# GBE1_PHY.net
KiCad netlist of a schematic drawn in Altium Designer
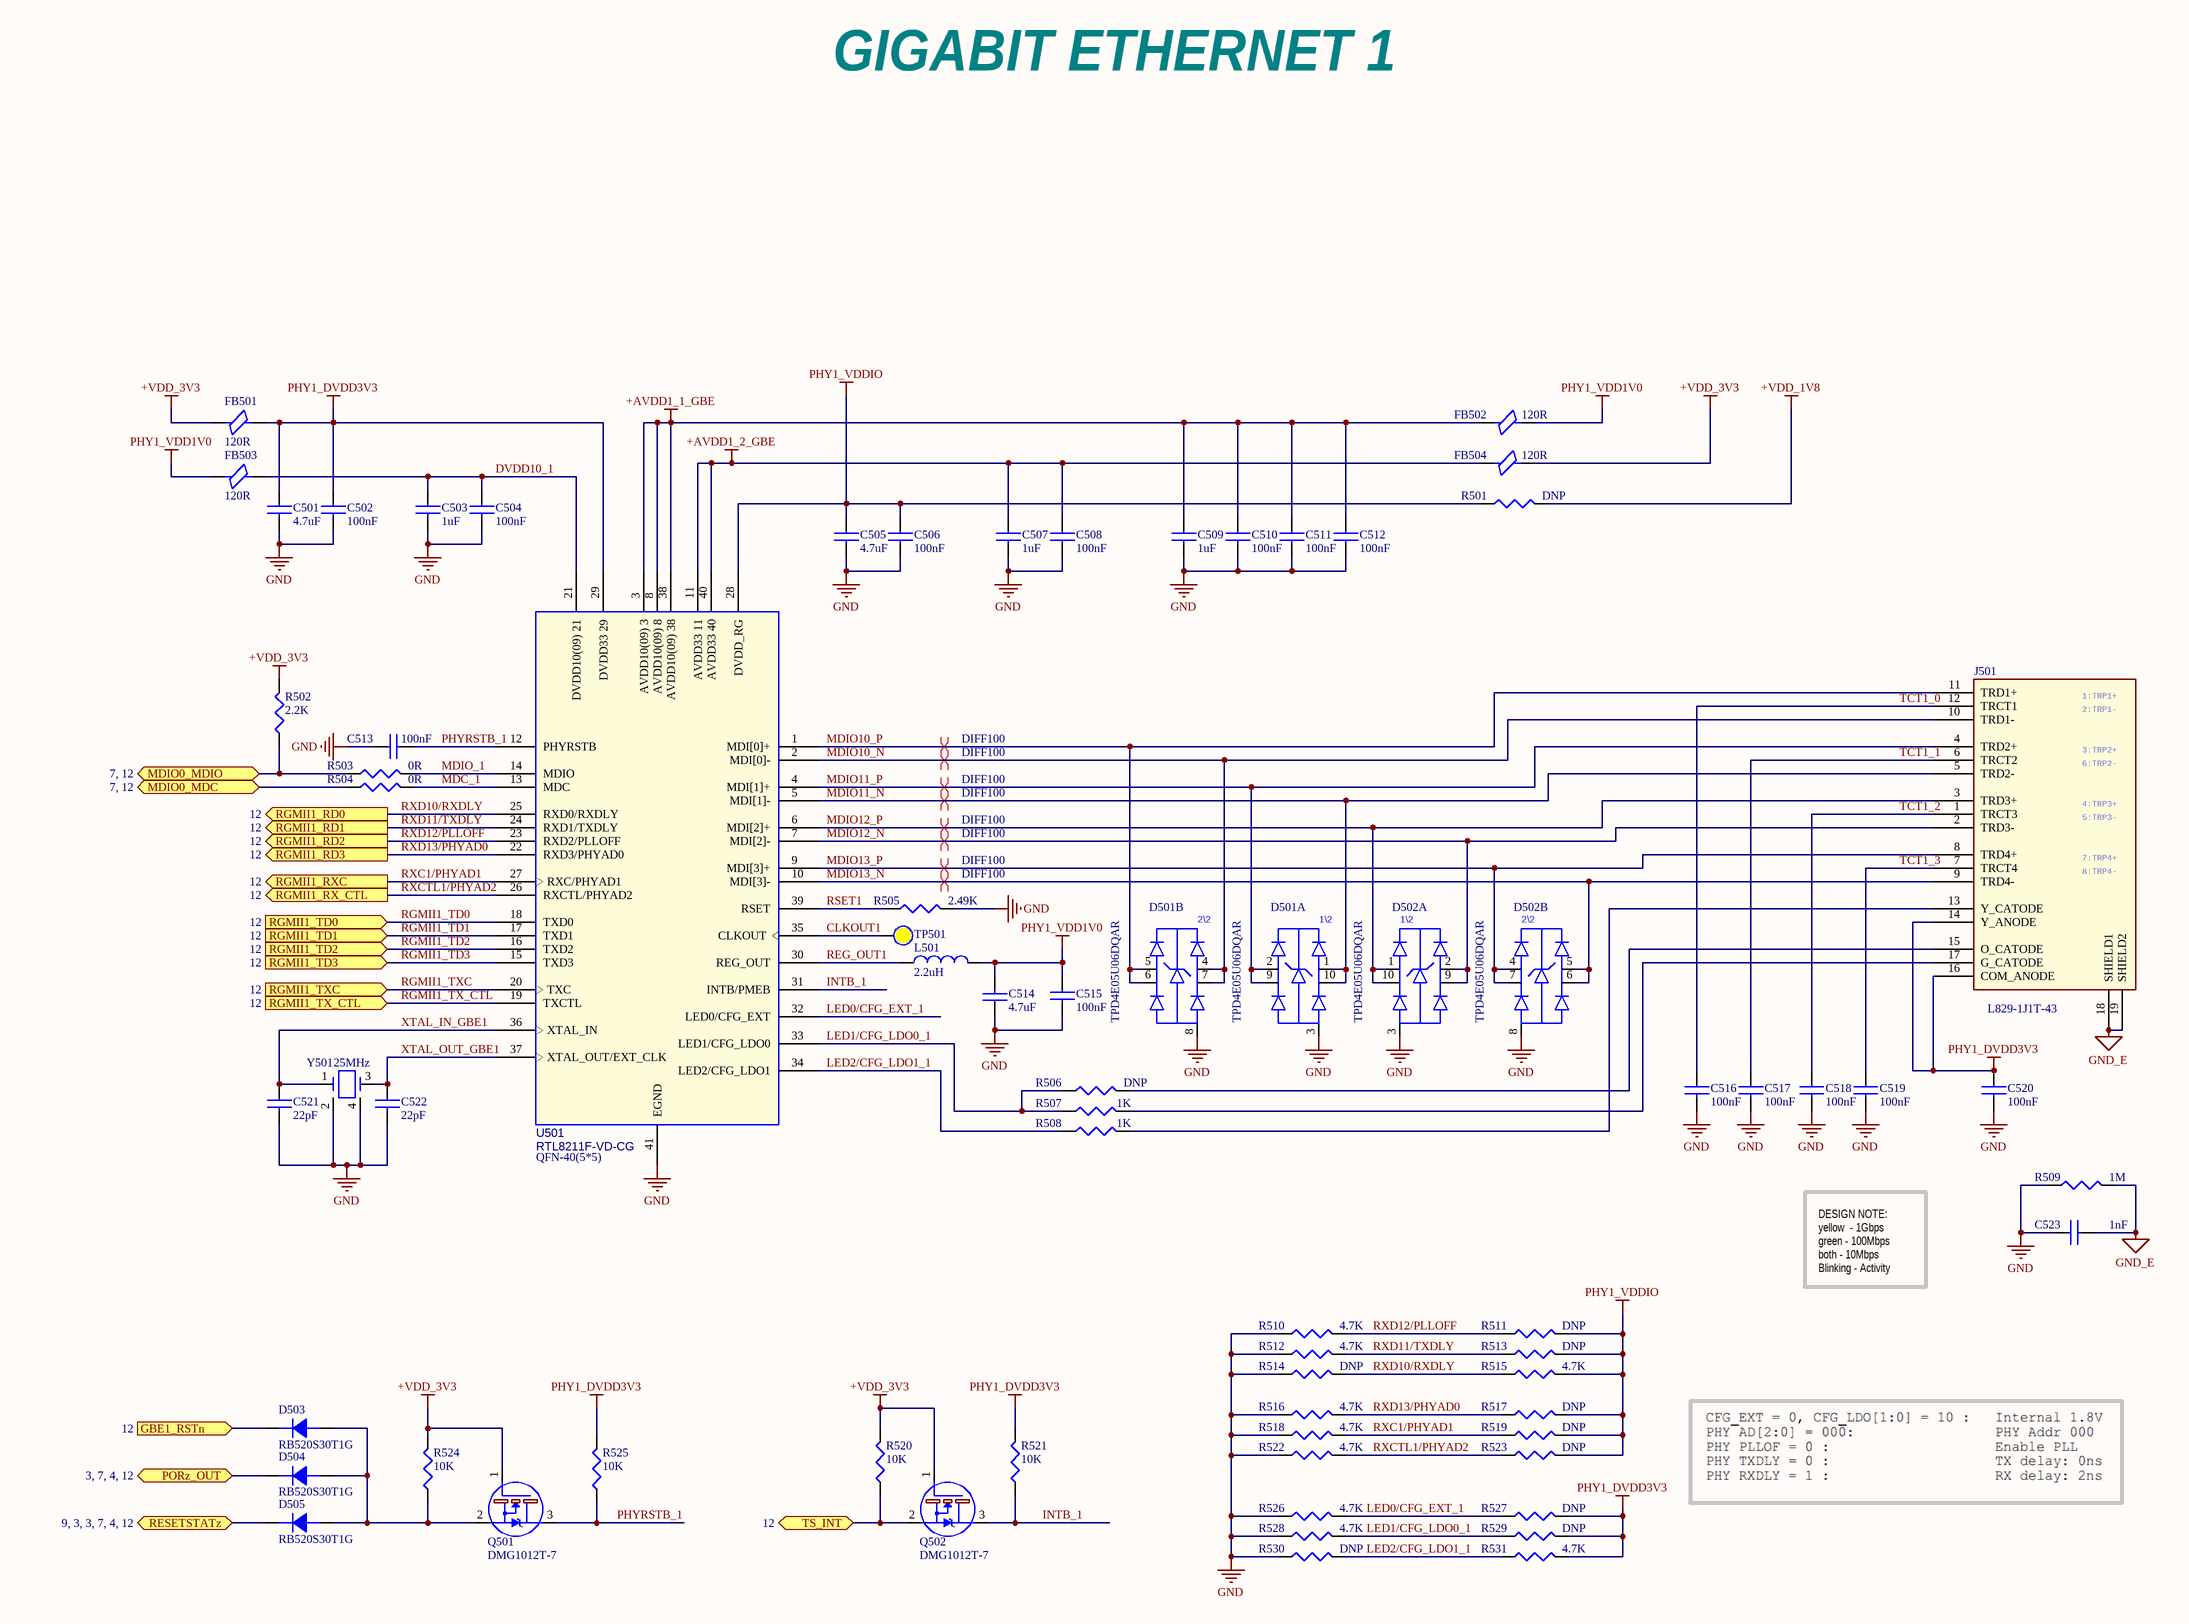
[diagram p0: GBE1 PHY.SchDoc]

(export (version "E")
  (design (tool "Eeschema 10.0.6"))
  (components
    (comp (ref "C501")
      (value "4.7uF")
      (footprint "C0402")
      (description "Multilayer Ceramic Capacitor, 4.7 uF, 6.3V, ± 10%, X5R, 0402 [1005 Metric]")
      (fields
        (field (name "MANUFACTURER") "Yageo")
        (field (name "MANUFACTURER PART NUMBER") "CC0402MRX5R5BB475")
      )
      (libsource (lib "Schlib SOM AM625") (part "CC0402MRX5R5BB475"))
    )
    (comp (ref "C502")
      (value "100nF")
      (footprint "C0201")
      (description "Multilayer Ceramic Capacitor, 0.1 uF, 16 V, ± 10%, X5R, 0201 [0603 Metric]")
      (fields
        (field (name "MANUFACTURER") "Yageo")
        (field (name "MANUFACTURER PART NUMBER") "CC0201KRX5R6BB104")
      )
      (libsource (lib "Schlib SOM AM625") (part "CC0201KRX5R6BB104"))
    )
    (comp (ref "C503")
      (value "1uF")
      (footprint "C0201")
      (description "1 µF ±20% 6.3V Ceramic Capacitor X5R 0201 (0603 Metric)")
      (fields
        (field (name "MANUFACTURER") "Yageo")
        (field (name "MANUFACTURER PART NUMBER") "CC0201MRX5R5BB105")
      )
      (libsource (lib "Schlib SOM AM625") (part "CC0201MRX5R5BB105"))
    )
    (comp (ref "C504")
      (value "100nF")
      (footprint "C0201")
      (description "Multilayer Ceramic Capacitor, 0.1 uF, 16 V, ± 10%, X5R, 0201 [0603 Metric]")
      (fields
        (field (name "MANUFACTURER") "Yageo")
        (field (name "MANUFACTURER PART NUMBER") "CC0201KRX5R6BB104")
      )
      (libsource (lib "Schlib SOM AM625") (part "CC0201KRX5R6BB104"))
    )
    (comp (ref "C505")
      (value "4.7uF")
      (footprint "C0402")
      (description "Multilayer Ceramic Capacitor, 4.7 uF, 6.3V, ± 10%, X5R, 0402 [1005 Metric]")
      (fields
        (field (name "MANUFACTURER") "Yageo")
        (field (name "MANUFACTURER PART NUMBER") "CC0402MRX5R5BB475")
      )
      (libsource (lib "Schlib SOM AM625") (part "CC0402MRX5R5BB475"))
    )
    (comp (ref "C506")
      (value "100nF")
      (footprint "C0201")
      (description "Multilayer Ceramic Capacitor, 0.1 uF, 16 V, ± 10%, X5R, 0201 [0603 Metric]")
      (fields
        (field (name "MANUFACTURER") "Yageo")
        (field (name "MANUFACTURER PART NUMBER") "CC0201KRX5R6BB104")
      )
      (libsource (lib "Schlib SOM AM625") (part "CC0201KRX5R6BB104"))
    )
    (comp (ref "C507")
      (value "1uF")
      (footprint "C0201")
      (description "1 µF ±20% 6.3V Ceramic Capacitor X5R 0201 (0603 Metric)")
      (fields
        (field (name "MANUFACTURER") "Yageo")
        (field (name "MANUFACTURER PART NUMBER") "CC0201MRX5R5BB105")
      )
      (libsource (lib "Schlib SOM AM625") (part "CC0201MRX5R5BB105"))
    )
    (comp (ref "C508")
      (value "100nF")
      (footprint "C0201")
      (description "Multilayer Ceramic Capacitor, 0.1 uF, 16 V, ± 10%, X5R, 0201 [0603 Metric]")
      (fields
        (field (name "MANUFACTURER") "Yageo")
        (field (name "MANUFACTURER PART NUMBER") "CC0201KRX5R6BB104")
      )
      (libsource (lib "Schlib SOM AM625") (part "CC0201KRX5R6BB104"))
    )
    (comp (ref "C509")
      (value "1uF")
      (footprint "C0201")
      (description "1 µF ±20% 6.3V Ceramic Capacitor X5R 0201 (0603 Metric)")
      (fields
        (field (name "MANUFACTURER") "Yageo")
        (field (name "MANUFACTURER PART NUMBER") "CC0201MRX5R5BB105")
      )
      (libsource (lib "Schlib SOM AM625") (part "CC0201MRX5R5BB105"))
    )
    (comp (ref "C510")
      (value "100nF")
      (footprint "C0201")
      (description "Multilayer Ceramic Capacitor, 0.1 uF, 16 V, ± 10%, X5R, 0201 [0603 Metric]")
      (fields
        (field (name "MANUFACTURER") "Yageo")
        (field (name "MANUFACTURER PART NUMBER") "CC0201KRX5R6BB104")
      )
      (libsource (lib "Schlib SOM AM625") (part "CC0201KRX5R6BB104"))
    )
    (comp (ref "C511")
      (value "100nF")
      (footprint "C0201")
      (description "Multilayer Ceramic Capacitor, 0.1 uF, 16 V, ± 10%, X5R, 0201 [0603 Metric]")
      (fields
        (field (name "MANUFACTURER") "Yageo")
        (field (name "MANUFACTURER PART NUMBER") "CC0201KRX5R6BB104")
      )
      (libsource (lib "Schlib SOM AM625") (part "CC0201KRX5R6BB104"))
    )
    (comp (ref "C512")
      (value "100nF")
      (footprint "C0201")
      (description "Multilayer Ceramic Capacitor, 0.1 uF, 16 V, ± 10%, X5R, 0201 [0603 Metric]")
      (fields
        (field (name "MANUFACTURER") "Yageo")
        (field (name "MANUFACTURER PART NUMBER") "CC0201KRX5R6BB104")
      )
      (libsource (lib "Schlib SOM AM625") (part "CC0201KRX5R6BB104"))
    )
    (comp (ref "C513")
      (value "100nF")
      (footprint "C0201")
      (description "Multilayer Ceramic Capacitor, 0.1 uF, 16 V, ± 10%, X5R, 0201 [0603 Metric]")
      (fields
        (field (name "MANUFACTURER") "Yageo")
        (field (name "MANUFACTURER PART NUMBER") "CC0201KRX5R6BB104")
      )
      (libsource (lib "Schlib SOM AM625") (part "CC0201KRX5R6BB104"))
    )
    (comp (ref "C514")
      (value "4.7uF")
      (footprint "C0402")
      (description "Multilayer Ceramic Capacitor, 4.7 uF, 6.3V, ± 10%, X5R, 0402 [1005 Metric]")
      (fields
        (field (name "MANUFACTURER") "Yageo")
        (field (name "MANUFACTURER PART NUMBER") "CC0402MRX5R5BB475")
      )
      (libsource (lib "Schlib SOM AM625") (part "CC0402MRX5R5BB475"))
    )
    (comp (ref "C515")
      (value "100nF")
      (footprint "C0201")
      (description "Multilayer Ceramic Capacitor, 0.1 uF, 16 V, ± 10%, X5R, 0201 [0603 Metric]")
      (fields
        (field (name "MANUFACTURER") "Yageo")
        (field (name "MANUFACTURER PART NUMBER") "CC0201KRX5R6BB104")
      )
      (libsource (lib "Schlib SOM AM625") (part "CC0201KRX5R6BB104"))
    )
    (comp (ref "C516")
      (value "100nF")
      (footprint "C0402")
      (description "Multilayer Ceramic Capacitor, 0.1 uF, 50 V, ± 10%, X5R, 0402 [1005 Metric]")
      (fields
        (field (name "MANUFACTURER") "TDK")
        (field (name "MANUFACTURER PART NUMBER") "C1005X5R1H104K050BB")
      )
      (libsource (lib "Schlib SOM AM625") (part "C1005X5R1H104K050BB"))
    )
    (comp (ref "C517")
      (value "100nF")
      (footprint "C0402")
      (description "Multilayer Ceramic Capacitor, 0.1 uF, 50 V, ± 10%, X5R, 0402 [1005 Metric]")
      (fields
        (field (name "MANUFACTURER") "TDK")
        (field (name "MANUFACTURER PART NUMBER") "C1005X5R1H104K050BB")
      )
      (libsource (lib "Schlib SOM AM625") (part "C1005X5R1H104K050BB"))
    )
    (comp (ref "C518")
      (value "100nF")
      (footprint "C0402")
      (description "Multilayer Ceramic Capacitor, 0.1 uF, 50 V, ± 10%, X5R, 0402 [1005 Metric]")
      (fields
        (field (name "MANUFACTURER") "TDK")
        (field (name "MANUFACTURER PART NUMBER") "C1005X5R1H104K050BB")
      )
      (libsource (lib "Schlib SOM AM625") (part "C1005X5R1H104K050BB"))
    )
    (comp (ref "C519")
      (value "100nF")
      (footprint "C0402")
      (description "Multilayer Ceramic Capacitor, 0.1 uF, 50 V, ± 10%, X5R, 0402 [1005 Metric]")
      (fields
        (field (name "MANUFACTURER") "TDK")
        (field (name "MANUFACTURER PART NUMBER") "C1005X5R1H104K050BB")
      )
      (libsource (lib "Schlib SOM AM625") (part "C1005X5R1H104K050BB"))
    )
    (comp (ref "C520")
      (value "100nF")
      (footprint "C0402")
      (description "Multilayer Ceramic Capacitor, 0.1 uF, 50 V, ± 10%, X5R, 0402 [1005 Metric]")
      (fields
        (field (name "MANUFACTURER") "TDK")
        (field (name "MANUFACTURER PART NUMBER") "C1005X5R1H104K050BB")
      )
      (libsource (lib "Schlib SOM AM625") (part "C1005X5R1H104K050BB"))
    )
    (comp (ref "C521")
      (value "22pF")
      (footprint "C0201")
      (description "0201 22 pF 50 V ±5 % Tolerance NP0 SMT Multilayer Ceramic Capacitor")
      (fields
        (field (name "MANUFACTURER") "Yageo")
        (field (name "MANUFACTURER PART NUMBER") "CC0201JRNPO9BN220")
      )
      (libsource (lib "Schlib SOM AM625") (part "CC0201JRNPO9BN220"))
    )
    (comp (ref "C522")
      (value "22pF")
      (footprint "C0201")
      (description "0201 22 pF 50 V ±5 % Tolerance NP0 SMT Multilayer Ceramic Capacitor")
      (fields
        (field (name "MANUFACTURER") "Yageo")
        (field (name "MANUFACTURER PART NUMBER") "CC0201JRNPO9BN220")
      )
      (libsource (lib "Schlib SOM AM625") (part "CC0201JRNPO9BN220"))
    )
    (comp (ref "C523")
      (value "1nF")
      (footprint "C1206B/3216MM")
      (description "Cap Ceramic 0.001uF 1000V X7R 10% Pad SMD 1206 125°C Low ESR Automotive Medical T/R")
      (fields
        (field (name "MANUFACTURER") "KEMET")
        (field (name "MANUFACTURER PART NUMBER") "C1206C102KDRACAUTO")
      )
      (libsource (lib "Schlib SOM AM625") (part "C1206C102KDRACAUTO"))
    )
    (comp (ref "D501")
      (value "TPD4E05U06DQAR")
      (footprint "10-USON")
      (description "Quad 0.5-pF, 5.5-V, ±12-kV ESD protection diode for USB, HDMI & High Speed Interfaces")
      (fields (field (name "MANUFACTURER") "Texas Instruments"))
      (libsource (lib "Schlib SOM AM625") (part "TPD4E05U06DQAR"))
    )
    (comp (ref "D502")
      (value "TPD4E05U06DQAR")
      (footprint "10-USON")
      (description "Quad 0.5-pF, 5.5-V, ±12-kV ESD protection diode for USB, HDMI & High Speed Interfaces")
      (fields (field (name "MANUFACTURER") "Texas Instruments"))
      (libsource (lib "Schlib SOM AM625") (part "TPD4E05U06DQAR"))
    )
    (comp (ref "D503")
      (value "RB520S30T1G")
      (footprint "sod_523")
      (description "Diode Schottky 30V 0.2A 2-Pin SOD-523 T/R - Product that comes on tape, but is not reeled")
      (fields (field (name "MANUFACTURER") "ON Semiconductor"))
      (libsource (lib "Schlib SOM AM625") (part "RB520S30T1G"))
    )
    (comp (ref "D504")
      (value "RB520S30T1G")
      (footprint "sod_523")
      (description "Diode Schottky 30V 0.2A 2-Pin SOD-523 T/R - Product that comes on tape, but is not reeled")
      (fields (field (name "MANUFACTURER") "ON Semiconductor"))
      (libsource (lib "Schlib SOM AM625") (part "RB520S30T1G"))
    )
    (comp (ref "D505")
      (value "RB520S30T1G")
      (footprint "sod_523")
      (description "Diode Schottky 30V 0.2A 2-Pin SOD-523 T/R - Product that comes on tape, but is not reeled")
      (fields (field (name "MANUFACTURER") "ON Semiconductor"))
      (libsource (lib "Schlib SOM AM625") (part "RB520S30T1G"))
    )
    (comp (ref "FB501")
      (value "120R")
      (footprint "FB0402")
      (description "Ferrite Beads Multi-Layer 120Ohm 25% 100MHz 1.3A 0.09Ohm DCR 0402 Automotive T/R")
      (fields
        (field (name "MANUFACTURER") "Murata")
        (field (name "MANUFACTURER PART NUMBER") "BLM15PD121SZ1D")
      )
      (libsource (lib "Schlib SOM AM625") (part "BLM15PD121SZ1D"))
    )
    (comp (ref "FB502")
      (value "120R")
      (footprint "FB0402")
      (description "Ferrite Beads Multi-Layer 120Ohm 25% 100MHz 1.3A 0.09Ohm DCR 0402 Automotive T/R")
      (fields
        (field (name "MANUFACTURER") "Murata")
        (field (name "MANUFACTURER PART NUMBER") "BLM15PD121SZ1D")
      )
      (libsource (lib "Schlib SOM AM625") (part "BLM15PD121SZ1D"))
    )
    (comp (ref "FB503")
      (value "120R")
      (footprint "FB0402")
      (description "Ferrite Beads Multi-Layer 120Ohm 25% 100MHz 1.3A 0.09Ohm DCR 0402 Automotive T/R")
      (fields
        (field (name "MANUFACTURER") "Murata")
        (field (name "MANUFACTURER PART NUMBER") "BLM15PD121SZ1D")
      )
      (libsource (lib "Schlib SOM AM625") (part "BLM15PD121SZ1D"))
    )
    (comp (ref "FB504")
      (value "120R")
      (footprint "FB0402")
      (description "Ferrite Beads Multi-Layer 120Ohm 25% 100MHz 1.3A 0.09Ohm DCR 0402 Automotive T/R")
      (fields
        (field (name "MANUFACTURER") "Murata")
        (field (name "MANUFACTURER PART NUMBER") "BLM15PD121SZ1D")
      )
      (libsource (lib "Schlib SOM AM625") (part "BLM15PD121SZ1D"))
    )
    (comp (ref "J501")
      (value "L829-1J1T-43")
      (footprint "L829-1J1T-43")
      (description "CONN MAGJACK 1PORT SHLD 1000BT")
      (fields
        (field (name "MANUFACTURER") "Bel Fuse Inc")
        (field (name ".CHECKED PCB") "RF")
        (field (name ".CHECKED SCH") "RF")
      )
      (libsource (lib "Schlib SOM AM625") (part "L829-1J1T-43"))
    )
    (comp (ref "L501")
      (value "2.2uH")
      (footprint "l2016")
      (description "Inductor Power Shielded Wirewound 2.2uH 20% 1MHz Metal 1.4A 0.168Ohm DCR 0806 T/R")
      (fields
        (field (name "MANUFACTURER") "Murata")
        (field (name "MANUFACTURER PART NUMBER") "DFE201610P-2R2M=P2")
      )
      (libsource (lib "Schlib SOM AM625") (part "DFE201610P-2R2M=P2"))
    )
    (comp (ref "Q501")
      (value "DMG1012T-7")
      (footprint "sot_523")
      (description "Transistor MOSFET NTR4003NT1G, SOT23, ON Semi")
      (fields (field (name "MANUFACTURER") "Diodes"))
      (libsource (lib "Schlib SOM AM625") (part "DMG1012T-7"))
    )
    (comp (ref "Q502")
      (value "DMG1012T-7")
      (footprint "sot_523")
      (description "Transistor MOSFET NTR4003NT1G, SOT23, ON Semi")
      (fields (field (name "MANUFACTURER") "Diodes"))
      (libsource (lib "Schlib SOM AM625") (part "DMG1012T-7"))
    )
    (comp (ref "R501")
      (value "DNP")
      (footprint "R0402")
      (description "Zero Ohm Resistor, Jumper, 0402 [1005 Metric], Thick Film, 63 mW, 1 A, Surface Mount")
      (fields
        (field (name "MANUFACTURER") "Yageo")
        (field (name "MANUFACTURER PART NUMBER") "RC0402JR-070RL")
      )
      (libsource (lib "Schlib SOM AM625") (part "RC0402JR-070RL"))
    )
    (comp (ref "R502")
      (value "2.2K")
      (footprint "R0201")
      (description "SMD Chip Resistor, 2.2 kOhm, ± 1%, 50 mW, 0201 [0603 Metric], Thick Film, General Purpose")
      (fields
        (field (name "MANUFACTURER") "Yageo")
        (field (name "MANUFACTURER PART NUMBER") "RC0201FR-072K2L")
      )
      (libsource (lib "Schlib SOM AM625") (part "RC0201FR-072K2L"))
    )
    (comp (ref "R503")
      (value "0R")
      (footprint "R0201")
      (description "Zero Ohm Resistor, Jumper, 0201 [0603 Metric], Thick Film, 50 mW, 500 mA, Surface Mount")
      (fields
        (field (name "MANUFACTURER") "Yageo")
        (field (name "MANUFACTURER PART NUMBER") "RC0201JR-070RL")
      )
      (libsource (lib "Schlib SOM AM625") (part "RC0201JR-070RL"))
    )
    (comp (ref "R504")
      (value "0R")
      (footprint "R0201")
      (description "Zero Ohm Resistor, Jumper, 0201 [0603 Metric], Thick Film, 50 mW, 500 mA, Surface Mount")
      (fields
        (field (name "MANUFACTURER") "Yageo")
        (field (name "MANUFACTURER PART NUMBER") "RC0201JR-070RL")
      )
      (libsource (lib "Schlib SOM AM625") (part "RC0201JR-070RL"))
    )
    (comp (ref "R505")
      (value "2.49K")
      (footprint "R0201")
      (description "SMD Chip Resistor, 2.49 kOhm, ± 1%, 50 mW, 0201 [0603 Metric], Thick Film, General Purpose")
      (fields
        (field (name "MANUFACTURER") "Yageo")
        (field (name "MANUFACTURER PART NUMBER") "RC0201FR-072K49L")
      )
      (libsource (lib "Schlib SOM AM625") (part "RC0201FR-072K49L"))
    )
    (comp (ref "R506")
      (value "DNP")
      (footprint "R0402")
      (description "Zero Ohm Resistor, Jumper, 0402 [1005 Metric], Thick Film, 63 mW, 1 A, Surface Mount")
      (fields
        (field (name "MANUFACTURER") "Yageo")
        (field (name "MANUFACTURER PART NUMBER") "RC0402JR-070RL")
      )
      (libsource (lib "Schlib SOM AM625") (part "RC0402JR-070RL"))
    )
    (comp (ref "R507")
      (value "1K")
      (footprint "R0402")
      (description "SMD Chip Resistor, 1 kOhm, ± 1%, 63 mW, 0402 [1005 Metric], Thick Film, General Purpose")
      (fields
        (field (name "MANUFACTURER") "Yageo")
        (field (name "MANUFACTURER PART NUMBER") "RC0402FR-071KL")
      )
      (libsource (lib "Schlib SOM AM625") (part "RC0402FR-071KL"))
    )
    (comp (ref "R508")
      (value "1K")
      (footprint "R0402")
      (description "SMD Chip Resistor, 1 kOhm, ± 1%, 63 mW, 0402 [1005 Metric], Thick Film, General Purpose")
      (fields
        (field (name "MANUFACTURER") "Yageo")
        (field (name "MANUFACTURER PART NUMBER") "RC0402FR-071KL")
      )
      (libsource (lib "Schlib SOM AM625") (part "RC0402FR-071KL"))
    )
    (comp (ref "R509")
      (value "1M")
      (footprint "R1206B/3216MM")
      (description "SMD Chip Resistor, 1 MOhm, ± 1%, 250 mW, 1206 [3216 Metric], Thick Film, General Purpose")
      (fields
        (field (name "MANUFACTURER") "Yageo")
        (field (name "MANUFACTURER PART NUMBER") "RC1206FR-071ML")
      )
      (libsource (lib "Schlib SOM AM625") (part "RC1206FR-071ML"))
    )
    (comp (ref "R510")
      (value "4.7K")
      (footprint "R0201")
      (description "SMD Chip Resistor, 4.7 kOhm, ± 5%, 50 mW, 0201 [0603 Metric], Thick Film, General Purpose")
      (fields
        (field (name "MANUFACTURER") "Yageo")
        (field (name "MANUFACTURER PART NUMBER") "RC0201JR-074K7L")
      )
      (libsource (lib "Schlib SOM AM625") (part "RC0201JR-074K7L"))
    )
    (comp (ref "R511")
      (value "DNP")
      (footprint "R0201")
      (description "SMD Chip Resistor, 4.7 kOhm, ± 5%, 50 mW, 0201 [0603 Metric], Thick Film, General Purpose")
      (fields
        (field (name "MANUFACTURER") "Yageo")
        (field (name "MANUFACTURER PART NUMBER") "RC0201JR-074K7L")
      )
      (libsource (lib "Schlib SOM AM625") (part "RC0201JR-074K7L"))
    )
    (comp (ref "R512")
      (value "4.7K")
      (footprint "R0201")
      (description "SMD Chip Resistor, 4.7 kOhm, ± 5%, 50 mW, 0201 [0603 Metric], Thick Film, General Purpose")
      (fields
        (field (name "MANUFACTURER") "Yageo")
        (field (name "MANUFACTURER PART NUMBER") "RC0201JR-074K7L")
      )
      (libsource (lib "Schlib SOM AM625") (part "RC0201JR-074K7L"))
    )
    (comp (ref "R513")
      (value "DNP")
      (footprint "R0201")
      (description "SMD Chip Resistor, 4.7 kOhm, ± 5%, 50 mW, 0201 [0603 Metric], Thick Film, General Purpose")
      (fields
        (field (name "MANUFACTURER") "Yageo")
        (field (name "MANUFACTURER PART NUMBER") "RC0201JR-074K7L")
      )
      (libsource (lib "Schlib SOM AM625") (part "RC0201JR-074K7L"))
    )
    (comp (ref "R514")
      (value "DNP")
      (footprint "R0201")
      (description "SMD Chip Resistor, 4.7 kOhm, ± 5%, 50 mW, 0201 [0603 Metric], Thick Film, General Purpose")
      (fields
        (field (name "MANUFACTURER") "Yageo")
        (field (name "MANUFACTURER PART NUMBER") "RC0201JR-074K7L")
      )
      (libsource (lib "Schlib SOM AM625") (part "RC0201JR-074K7L"))
    )
    (comp (ref "R515")
      (value "4.7K")
      (footprint "R0201")
      (description "SMD Chip Resistor, 4.7 kOhm, ± 5%, 50 mW, 0201 [0603 Metric], Thick Film, General Purpose")
      (fields
        (field (name "MANUFACTURER") "Yageo")
        (field (name "MANUFACTURER PART NUMBER") "RC0201JR-074K7L")
      )
      (libsource (lib "Schlib SOM AM625") (part "RC0201JR-074K7L"))
    )
    (comp (ref "R516")
      (value "4.7K")
      (footprint "R0201")
      (description "SMD Chip Resistor, 4.7 kOhm, ± 5%, 50 mW, 0201 [0603 Metric], Thick Film, General Purpose")
      (fields
        (field (name "MANUFACTURER") "Yageo")
        (field (name "MANUFACTURER PART NUMBER") "RC0201JR-074K7L")
      )
      (libsource (lib "Schlib SOM AM625") (part "RC0201JR-074K7L"))
    )
    (comp (ref "R517")
      (value "DNP")
      (footprint "R0201")
      (description "SMD Chip Resistor, 4.7 kOhm, ± 5%, 50 mW, 0201 [0603 Metric], Thick Film, General Purpose")
      (fields
        (field (name "MANUFACTURER") "Yageo")
        (field (name "MANUFACTURER PART NUMBER") "RC0201JR-074K7L")
      )
      (libsource (lib "Schlib SOM AM625") (part "RC0201JR-074K7L"))
    )
    (comp (ref "R518")
      (value "4.7K")
      (footprint "R0201")
      (description "SMD Chip Resistor, 4.7 kOhm, ± 5%, 50 mW, 0201 [0603 Metric], Thick Film, General Purpose")
      (fields
        (field (name "MANUFACTURER") "Yageo")
        (field (name "MANUFACTURER PART NUMBER") "RC0201JR-074K7L")
      )
      (libsource (lib "Schlib SOM AM625") (part "RC0201JR-074K7L"))
    )
    (comp (ref "R519")
      (value "DNP")
      (footprint "R0201")
      (description "SMD Chip Resistor, 4.7 kOhm, ± 5%, 50 mW, 0201 [0603 Metric], Thick Film, General Purpose")
      (fields
        (field (name "MANUFACTURER") "Yageo")
        (field (name "MANUFACTURER PART NUMBER") "RC0201JR-074K7L")
      )
      (libsource (lib "Schlib SOM AM625") (part "RC0201JR-074K7L"))
    )
    (comp (ref "R520")
      (value "10K")
      (footprint "R0201")
      (description "SMD Chip Resistor, 10 kOhm, ± 1%, 50 mW, 0201 [0603 Metric], Thick Film, General Purpose")
      (fields
        (field (name "MANUFACTURER") "Yageo")
        (field (name "MANUFACTURER PART NUMBER") "RC0201FR-0710KL")
      )
      (libsource (lib "Schlib SOM AM625") (part "RC0201FR-0710KL"))
    )
    (comp (ref "R521")
      (value "10K")
      (footprint "R0201")
      (description "SMD Chip Resistor, 10 kOhm, ± 1%, 50 mW, 0201 [0603 Metric], Thick Film, General Purpose")
      (fields
        (field (name "MANUFACTURER") "Yageo")
        (field (name "MANUFACTURER PART NUMBER") "RC0201FR-0710KL")
      )
      (libsource (lib "Schlib SOM AM625") (part "RC0201FR-0710KL"))
    )
    (comp (ref "R522")
      (value "4.7K")
      (footprint "R0201")
      (description "SMD Chip Resistor, 4.7 kOhm, ± 5%, 50 mW, 0201 [0603 Metric], Thick Film, General Purpose")
      (fields
        (field (name "MANUFACTURER") "Yageo")
        (field (name "MANUFACTURER PART NUMBER") "RC0201JR-074K7L")
      )
      (libsource (lib "Schlib SOM AM625") (part "RC0201JR-074K7L"))
    )
    (comp (ref "R523")
      (value "DNP")
      (footprint "R0201")
      (description "SMD Chip Resistor, 4.7 kOhm, ± 5%, 50 mW, 0201 [0603 Metric], Thick Film, General Purpose")
      (fields
        (field (name "MANUFACTURER") "Yageo")
        (field (name "MANUFACTURER PART NUMBER") "RC0201JR-074K7L")
      )
      (libsource (lib "Schlib SOM AM625") (part "RC0201JR-074K7L"))
    )
    (comp (ref "R524")
      (value "10K")
      (footprint "R0201")
      (description "SMD Chip Resistor, 10 kOhm, ± 1%, 50 mW, 0201 [0603 Metric], Thick Film, General Purpose")
      (fields
        (field (name "MANUFACTURER") "Yageo")
        (field (name "MANUFACTURER PART NUMBER") "RC0201FR-0710KL")
      )
      (libsource (lib "Schlib SOM AM625") (part "RC0201FR-0710KL"))
    )
    (comp (ref "R525")
      (value "10K")
      (footprint "R0201")
      (description "SMD Chip Resistor, 10 kOhm, ± 1%, 50 mW, 0201 [0603 Metric], Thick Film, General Purpose")
      (fields
        (field (name "MANUFACTURER") "Yageo")
        (field (name "MANUFACTURER PART NUMBER") "RC0201FR-0710KL")
      )
      (libsource (lib "Schlib SOM AM625") (part "RC0201FR-0710KL"))
    )
    (comp (ref "R526")
      (value "4.7K")
      (footprint "R0201")
      (description "SMD Chip Resistor, 4.7 kOhm, ± 5%, 50 mW, 0201 [0603 Metric], Thick Film, General Purpose")
      (fields
        (field (name "MANUFACTURER") "Yageo")
        (field (name "MANUFACTURER PART NUMBER") "RC0201JR-074K7L")
      )
      (libsource (lib "Schlib SOM AM625") (part "RC0201JR-074K7L"))
    )
    (comp (ref "R527")
      (value "DNP")
      (footprint "R0201")
      (description "SMD Chip Resistor, 4.7 kOhm, ± 5%, 50 mW, 0201 [0603 Metric], Thick Film, General Purpose")
      (fields
        (field (name "MANUFACTURER") "Yageo")
        (field (name "MANUFACTURER PART NUMBER") "RC0201JR-074K7L")
      )
      (libsource (lib "Schlib SOM AM625") (part "RC0201JR-074K7L"))
    )
    (comp (ref "R528")
      (value "4.7K")
      (footprint "R0201")
      (description "SMD Chip Resistor, 4.7 kOhm, ± 5%, 50 mW, 0201 [0603 Metric], Thick Film, General Purpose")
      (fields
        (field (name "MANUFACTURER") "Yageo")
        (field (name "MANUFACTURER PART NUMBER") "RC0201JR-074K7L")
      )
      (libsource (lib "Schlib SOM AM625") (part "RC0201JR-074K7L"))
    )
    (comp (ref "R529")
      (value "DNP")
      (footprint "R0201")
      (description "SMD Chip Resistor, 4.7 kOhm, ± 5%, 50 mW, 0201 [0603 Metric], Thick Film, General Purpose")
      (fields
        (field (name "MANUFACTURER") "Yageo")
        (field (name "MANUFACTURER PART NUMBER") "RC0201JR-074K7L")
      )
      (libsource (lib "Schlib SOM AM625") (part "RC0201JR-074K7L"))
    )
    (comp (ref "R530")
      (value "DNP")
      (footprint "R0201")
      (description "SMD Chip Resistor, 4.7 kOhm, ± 5%, 50 mW, 0201 [0603 Metric], Thick Film, General Purpose")
      (fields
        (field (name "MANUFACTURER") "Yageo")
        (field (name "MANUFACTURER PART NUMBER") "RC0201JR-074K7L")
      )
      (libsource (lib "Schlib SOM AM625") (part "RC0201JR-074K7L"))
    )
    (comp (ref "R531")
      (value "4.7K")
      (footprint "R0201")
      (description "SMD Chip Resistor, 4.7 kOhm, ± 5%, 50 mW, 0201 [0603 Metric], Thick Film, General Purpose")
      (fields
        (field (name "MANUFACTURER") "Yageo")
        (field (name "MANUFACTURER PART NUMBER") "RC0201JR-074K7L")
      )
      (libsource (lib "Schlib SOM AM625") (part "RC0201JR-074K7L"))
    )
    (comp (ref "TP501")
      (value "~")
      (footprint "Test Point 1 MM")
      (description "Test Point")
      (libsource (lib "BYTECH_HW_LIB_2019") (part "Test Point"))
    )
    (comp (ref "U501")
      (value "RTL8211F-VD-CG")
      (footprint "qfn40_0D4_5x5mm")
      (description "IC, Interface, Ethernet, RTL8211F-VD-CG, QFN-40(5*5)")
      (fields
        (field (name "MANUFACTURER") "Realtek")
        (field (name "PACKAGE SIZE") "QFN-40(5*5)")
        (field (name "Comment") "RTL8211")
      )
      (libsource (lib "Schlib SOM AM625") (part "RTL8211"))
    )
    (comp (ref "Y501")
      (value "25MHz")
      (footprint "x4-smd-3_2x2_5x1_0mm")
      (description "Crystal, 25MHZ, 18PF, SMD")
      (fields (field (name "MANUFACTURER") "IQD") (field (name "MANUFACTURER PART NUMBER") "LFXTAL055299"))
      (libsource (lib "Schlib SOM AM625") (part "LFXTAL055299"))
    )
  )
  (nets
    (net (code "1") (name "+AVDD1_1_GBE") (class "Default")
      (node (ref "C509") (pin "1") (pinfunction "1_1") (pintype "passive"))
      (node (ref "C510") (pin "1") (pinfunction "1_1") (pintype "passive"))
      (node (ref "C511") (pin "1") (pinfunction "1_1") (pintype "passive"))
      (node (ref "C512") (pin "1") (pinfunction "1_1") (pintype "passive"))
      (node (ref "FB502") (pin "1") (pinfunction "1_1") (pintype "passive"))
      (node (ref "U501") (pin "3") (pinfunction "AVDD10(09)_3_3") (pintype "power_in"))
      (node (ref "U501") (pin "38") (pinfunction "AVDD10(09)_38_38") (pintype "power_in"))
      (node (ref "U501") (pin "8") (pinfunction "AVDD10(09)_8_8") (pintype "power_in"))
    )
    (net (code "2") (name "+AVDD1_2_GBE") (class "Default")
      (node (ref "C507") (pin "1") (pinfunction "1_1") (pintype "passive"))
      (node (ref "C508") (pin "1") (pinfunction "1_1") (pintype "passive"))
      (node (ref "FB504") (pin "1") (pinfunction "1_1") (pintype "passive"))
      (node (ref "U501") (pin "11") (pinfunction "AVDD33_11_11") (pintype "power_in"))
      (node (ref "U501") (pin "40") (pinfunction "AVDD33_40_40") (pintype "power_in"))
    )
    (net (code "3") (name "+VDD_1V8") (class "Default")
      (node (ref "R501") (pin "2") (pinfunction "2_2") (pintype "passive"))
    )
    (net (code "4") (name "+VDD_3V3") (class "Default")
      (node (ref "FB501") (pin "1") (pinfunction "1_1") (pintype "passive"))
      (node (ref "FB504") (pin "2") (pinfunction "2_2") (pintype "passive"))
      (node (ref "Q501") (pin "1") (pinfunction "G_1") (pintype "passive"))
      (node (ref "Q502") (pin "1") (pinfunction "G_1") (pintype "passive"))
      (node (ref "R502") (pin "2") (pinfunction "2_2") (pintype "passive"))
      (node (ref "R520") (pin "2") (pinfunction "2_2") (pintype "passive"))
      (node (ref "R524") (pin "2") (pinfunction "2_2") (pintype "passive"))
    )
    (net (code "5") (name "/CLKOUT1") (class "Default")
      (node (ref "TP501") (pin "0") (pinfunction "0_0") (pintype "passive"))
      (node (ref "U501") (pin "35") (pinfunction "CLKOUT_35") (pintype "passive"))
    )
    (net (code "6") (name "/DVDD10_1") (class "Default")
      (node (ref "C503") (pin "1") (pinfunction "1_1") (pintype "passive"))
      (node (ref "C504") (pin "1") (pinfunction "1_1") (pintype "passive"))
      (node (ref "FB503") (pin "2") (pinfunction "2_2") (pintype "passive"))
      (node (ref "U501") (pin "21") (pinfunction "DVDD10(09)_21_21") (pintype "power_in"))
    )
    (net (code "7") (name "/GBE1_RSTn") (class "Default")
      (node (ref "D503") (pin "2") (pinfunction "C_2") (pintype "passive"))
    )
    (net (code "8") (name "/INTB_1") (class "Default")
      (node (ref "Q502") (pin "3") (pinfunction "D_3") (pintype "passive"))
      (node (ref "R521") (pin "1") (pinfunction "1_1") (pintype "passive"))
      (node (ref "U501") (pin "31") (pinfunction "INTB/PMEB_31") (pintype "passive"))
    )
    (net (code "9") (name "/LED0{slash}CFG_EXT_1") (class "Default")
      (node (ref "R526") (pin "2") (pinfunction "2_2") (pintype "passive"))
      (node (ref "R527") (pin "1") (pinfunction "1_1") (pintype "passive"))
      (node (ref "U501") (pin "32") (pinfunction "LED0/CFG_EXT_32") (pintype "passive"))
    )
    (net (code "10") (name "/LED1{slash}CFG_LDO0_1") (class "Default")
      (node (ref "R506") (pin "1") (pinfunction "1_1") (pintype "passive"))
      (node (ref "R507") (pin "1") (pinfunction "1_1") (pintype "passive"))
      (node (ref "R528") (pin "2") (pinfunction "2_2") (pintype "passive"))
      (node (ref "R529") (pin "1") (pinfunction "1_1") (pintype "passive"))
      (node (ref "U501") (pin "33") (pinfunction "LED1/CFG_LDO0_33") (pintype "passive"))
    )
    (net (code "11") (name "/LED2{slash}CFG_LDO1_1") (class "Default")
      (node (ref "R508") (pin "1") (pinfunction "1_1") (pintype "passive"))
      (node (ref "R530") (pin "2") (pinfunction "2_2") (pintype "passive"))
      (node (ref "R531") (pin "1") (pinfunction "1_1") (pintype "passive"))
      (node (ref "U501") (pin "34") (pinfunction "LED2/CFG_LDO1_34") (pintype "passive"))
    )
    (net (code "12") (name "/MDC_1") (class "Default")
      (node (ref "R504") (pin "2") (pinfunction "2_2") (pintype "passive"))
      (node (ref "U501") (pin "13") (pinfunction "MDC_13") (pintype "passive"))
    )
    (net (code "13") (name "/MDIO0_MDC") (class "Default")
      (node (ref "R504") (pin "1") (pinfunction "1_1") (pintype "passive"))
    )
    (net (code "14") (name "/MDIO0_MDIO") (class "Default")
      (node (ref "R502") (pin "1") (pinfunction "1_1") (pintype "passive"))
      (node (ref "R503") (pin "1") (pinfunction "1_1") (pintype "passive"))
    )
    (net (code "15") (name "/MDIO10_N") (class "Default")
      (node (ref "D501") (pin "4") (pinfunction "3A_4") (pintype "passive"))
      (node (ref "D501") (pin "7") (pinfunction "3B_7") (pintype "passive"))
      (node (ref "J501") (pin "10") (pinfunction "TRD1-_10") (pintype "passive"))
      (node (ref "U501") (pin "2") (pinfunction "MDI[0]-_2") (pintype "passive"))
    )
    (net (code "16") (name "/MDIO10_P") (class "Default")
      (node (ref "D501") (pin "5") (pinfunction "4A_5") (pintype "passive"))
      (node (ref "D501") (pin "6") (pinfunction "4B_6") (pintype "passive"))
      (node (ref "J501") (pin "11") (pinfunction "TRD1+_11") (pintype "passive"))
      (node (ref "U501") (pin "1") (pinfunction "MDI[0]+_1") (pintype "passive"))
    )
    (net (code "17") (name "/MDIO11_N") (class "Default")
      (node (ref "D501") (pin "1") (pinfunction "1A_1") (pintype "passive"))
      (node (ref "D501") (pin "10") (pinfunction "1B_10") (pintype "passive"))
      (node (ref "J501") (pin "5") (pinfunction "TRD2-_5") (pintype "passive"))
      (node (ref "U501") (pin "5") (pinfunction "MDI[1]-_5") (pintype "passive"))
    )
    (net (code "18") (name "/MDIO11_P") (class "Default")
      (node (ref "D501") (pin "2") (pinfunction "2A_2") (pintype "passive"))
      (node (ref "D501") (pin "9") (pinfunction "2B_9") (pintype "passive"))
      (node (ref "J501") (pin "4") (pinfunction "TRD2+_4") (pintype "passive"))
      (node (ref "U501") (pin "4") (pinfunction "MDI[1]+_4") (pintype "passive"))
    )
    (net (code "19") (name "/MDIO12_N") (class "Default")
      (node (ref "D502") (pin "2") (pinfunction "2A_2") (pintype "passive"))
      (node (ref "D502") (pin "9") (pinfunction "2B_9") (pintype "passive"))
      (node (ref "J501") (pin "2") (pinfunction "TRD3-_2") (pintype "passive"))
      (node (ref "U501") (pin "7") (pinfunction "MDI[2]-_7") (pintype "passive"))
    )
    (net (code "20") (name "/MDIO12_P") (class "Default")
      (node (ref "D502") (pin "1") (pinfunction "1A_1") (pintype "passive"))
      (node (ref "D502") (pin "10") (pinfunction "1B_10") (pintype "passive"))
      (node (ref "J501") (pin "3") (pinfunction "TRD3+_3") (pintype "passive"))
      (node (ref "U501") (pin "6") (pinfunction "MDI[2]+_6") (pintype "passive"))
    )
    (net (code "21") (name "/MDIO13_N") (class "Default")
      (node (ref "D502") (pin "5") (pinfunction "4A_5") (pintype "passive"))
      (node (ref "D502") (pin "6") (pinfunction "4B_6") (pintype "passive"))
      (node (ref "J501") (pin "9") (pinfunction "TRD4-_9") (pintype "passive"))
      (node (ref "U501") (pin "10") (pinfunction "MDI[3]-_10") (pintype "passive"))
    )
    (net (code "22") (name "/MDIO13_P") (class "Default")
      (node (ref "D502") (pin "4") (pinfunction "3A_4") (pintype "passive"))
      (node (ref "D502") (pin "7") (pinfunction "3B_7") (pintype "passive"))
      (node (ref "J501") (pin "8") (pinfunction "TRD4+_8") (pintype "passive"))
      (node (ref "U501") (pin "9") (pinfunction "MDI[3]+_9") (pintype "passive"))
    )
    (net (code "23") (name "/MDIO_1") (class "Default")
      (node (ref "R503") (pin "2") (pinfunction "2_2") (pintype "passive"))
      (node (ref "U501") (pin "14") (pinfunction "MDIO_14") (pintype "passive"))
    )
    (net (code "24") (name "/PHYRSTB_1") (class "Default")
      (node (ref "C513") (pin "2") (pinfunction "2_2") (pintype "passive"))
      (node (ref "Q501") (pin "3") (pinfunction "D_3") (pintype "passive"))
      (node (ref "R525") (pin "1") (pinfunction "1_1") (pintype "passive"))
      (node (ref "U501") (pin "12") (pinfunction "PHYRSTB_12") (pintype "passive"))
    )
    (net (code "25") (name "/PORz_OUT") (class "Default")
      (node (ref "D504") (pin "2") (pinfunction "C_2") (pintype "passive"))
    )
    (net (code "26") (name "/REG_OUT1") (class "Default")
      (node (ref "L501") (pin "1") (pinfunction "1_1") (pintype "passive"))
      (node (ref "U501") (pin "30") (pinfunction "REG_OUT_30") (pintype "power_in"))
    )
    (net (code "27") (name "/RESETSTATz") (class "Default")
      (node (ref "D505") (pin "2") (pinfunction "C_2") (pintype "passive"))
    )
    (net (code "28") (name "/RGMII1_TD0") (class "Default")
      (node (ref "U501") (pin "18") (pinfunction "TXD0_18") (pintype "passive"))
    )
    (net (code "29") (name "/RGMII1_TD1") (class "Default")
      (node (ref "U501") (pin "17") (pinfunction "TXD1_17") (pintype "passive"))
    )
    (net (code "30") (name "/RGMII1_TD2") (class "Default")
      (node (ref "U501") (pin "16") (pinfunction "TXD2_16") (pintype "passive"))
    )
    (net (code "31") (name "/RGMII1_TD3") (class "Default")
      (node (ref "U501") (pin "15") (pinfunction "TXD3_15") (pintype "passive"))
    )
    (net (code "32") (name "/RGMII1_TXC") (class "Default")
      (node (ref "U501") (pin "20") (pinfunction "TXC_20") (pintype "passive"))
    )
    (net (code "33") (name "/RGMII1_TX_CTL") (class "Default")
      (node (ref "U501") (pin "19") (pinfunction "TXCTL_19") (pintype "passive"))
    )
    (net (code "34") (name "/RSET1") (class "Default")
      (node (ref "R505") (pin "1") (pinfunction "1_1") (pintype "passive"))
      (node (ref "U501") (pin "39") (pinfunction "RSET_39") (pintype "passive"))
    )
    (net (code "35") (name "/RXC1{slash}PHYAD1") (class "Default")
      (node (ref "R518") (pin "2") (pinfunction "2_2") (pintype "passive"))
      (node (ref "R519") (pin "1") (pinfunction "1_1") (pintype "passive"))
      (node (ref "U501") (pin "27") (pinfunction "RXC/PHYAD1_27") (pintype "passive"))
    )
    (net (code "36") (name "/RXCTL1{slash}PHYAD2") (class "Default")
      (node (ref "R522") (pin "2") (pinfunction "2_2") (pintype "passive"))
      (node (ref "R523") (pin "1") (pinfunction "1_1") (pintype "passive"))
      (node (ref "U501") (pin "26") (pinfunction "RXCTL/PHYAD2_26") (pintype "passive"))
    )
    (net (code "37") (name "/RXD10{slash}RXDLY") (class "Default")
      (node (ref "R514") (pin "2") (pinfunction "2_2") (pintype "passive"))
      (node (ref "R515") (pin "1") (pinfunction "1_1") (pintype "passive"))
      (node (ref "U501") (pin "25") (pinfunction "RXD0/RXDLY_25") (pintype "passive"))
    )
    (net (code "38") (name "/RXD11{slash}TXDLY") (class "Default")
      (node (ref "R512") (pin "2") (pinfunction "2_2") (pintype "passive"))
      (node (ref "R513") (pin "1") (pinfunction "1_1") (pintype "passive"))
      (node (ref "U501") (pin "24") (pinfunction "RXD1/TXDLY_24") (pintype "passive"))
    )
    (net (code "39") (name "/RXD12{slash}PLLOFF") (class "Default")
      (node (ref "R510") (pin "2") (pinfunction "2_2") (pintype "passive"))
      (node (ref "R511") (pin "1") (pinfunction "1_1") (pintype "passive"))
      (node (ref "U501") (pin "23") (pinfunction "RXD2/PLLOFF_23") (pintype "passive"))
    )
    (net (code "40") (name "/RXD13{slash}PHYAD0") (class "Default")
      (node (ref "R516") (pin "2") (pinfunction "2_2") (pintype "passive"))
      (node (ref "R517") (pin "1") (pinfunction "1_1") (pintype "passive"))
      (node (ref "U501") (pin "22") (pinfunction "RXD3/PHYAD0_22") (pintype "passive"))
    )
    (net (code "41") (name "/TCT1_0") (class "Default")
      (node (ref "C516") (pin "1") (pinfunction "1_1") (pintype "passive"))
      (node (ref "J501") (pin "12") (pinfunction "TRCT1_12") (pintype "passive"))
    )
    (net (code "42") (name "/TCT1_1") (class "Default")
      (node (ref "C517") (pin "1") (pinfunction "1_1") (pintype "passive"))
      (node (ref "J501") (pin "6") (pinfunction "TRCT2_6") (pintype "passive"))
    )
    (net (code "43") (name "/TCT1_2") (class "Default")
      (node (ref "C518") (pin "1") (pinfunction "1_1") (pintype "passive"))
      (node (ref "J501") (pin "1") (pinfunction "TRCT3_1") (pintype "passive"))
    )
    (net (code "44") (name "/TCT1_3") (class "Default")
      (node (ref "C519") (pin "1") (pinfunction "1_1") (pintype "passive"))
      (node (ref "J501") (pin "7") (pinfunction "TRCT4_7") (pintype "passive"))
    )
    (net (code "45") (name "/TS_INT") (class "Default")
      (node (ref "Q502") (pin "2") (pinfunction "S_2") (pintype "passive"))
      (node (ref "R520") (pin "1") (pinfunction "1_1") (pintype "passive"))
    )
    (net (code "46") (name "/XTAL_IN_GBE1") (class "Default")
      (node (ref "C521") (pin "1") (pinfunction "1_1") (pintype "passive"))
      (node (ref "U501") (pin "36") (pinfunction "XTAL_IN_36") (pintype "passive"))
      (node (ref "Y501") (pin "1") (pinfunction "1_1") (pintype "passive"))
    )
    (net (code "47") (name "/XTAL_OUT_GBE1") (class "Default")
      (node (ref "C522") (pin "1") (pinfunction "1_1") (pintype "passive"))
      (node (ref "U501") (pin "37") (pinfunction "XTAL_OUT/EXT_CLK_37") (pintype "passive"))
      (node (ref "Y501") (pin "3") (pinfunction "3_3") (pintype "passive"))
    )
    (net (code "48") (name "GND") (class "Default")
      (node (ref "C501") (pin "2") (pinfunction "2_2") (pintype "passive"))
      (node (ref "C502") (pin "2") (pinfunction "2_2") (pintype "passive"))
      (node (ref "C503") (pin "2") (pinfunction "2_2") (pintype "passive"))
      (node (ref "C504") (pin "2") (pinfunction "2_2") (pintype "passive"))
      (node (ref "C505") (pin "2") (pinfunction "2_2") (pintype "passive"))
      (node (ref "C506") (pin "2") (pinfunction "2_2") (pintype "passive"))
      (node (ref "C507") (pin "2") (pinfunction "2_2") (pintype "passive"))
      (node (ref "C508") (pin "2") (pinfunction "2_2") (pintype "passive"))
      (node (ref "C509") (pin "2") (pinfunction "2_2") (pintype "passive"))
      (node (ref "C510") (pin "2") (pinfunction "2_2") (pintype "passive"))
      (node (ref "C511") (pin "2") (pinfunction "2_2") (pintype "passive"))
      (node (ref "C512") (pin "2") (pinfunction "2_2") (pintype "passive"))
      (node (ref "C513") (pin "1") (pinfunction "1_1") (pintype "passive"))
      (node (ref "C514") (pin "1") (pinfunction "1_1") (pintype "passive"))
      (node (ref "C515") (pin "2") (pinfunction "2_2") (pintype "passive"))
      (node (ref "C516") (pin "2") (pinfunction "2_2") (pintype "passive"))
      (node (ref "C517") (pin "2") (pinfunction "2_2") (pintype "passive"))
      (node (ref "C518") (pin "2") (pinfunction "2_2") (pintype "passive"))
      (node (ref "C519") (pin "2") (pinfunction "2_2") (pintype "passive"))
      (node (ref "C520") (pin "2") (pinfunction "2_2") (pintype "passive"))
      (node (ref "C521") (pin "2") (pinfunction "2_2") (pintype "passive"))
      (node (ref "C522") (pin "2") (pinfunction "2_2") (pintype "passive"))
      (node (ref "C523") (pin "1") (pinfunction "1_1") (pintype "passive"))
      (node (ref "D501") (pin "3") (pinfunction "GND1_3") (pintype "passive"))
      (node (ref "D501") (pin "8") (pinfunction "GND1_8") (pintype "passive"))
      (node (ref "D502") (pin "3") (pinfunction "GND1_3") (pintype "passive"))
      (node (ref "D502") (pin "8") (pinfunction "GND1_8") (pintype "passive"))
      (node (ref "R505") (pin "2") (pinfunction "2_2") (pintype "passive"))
      (node (ref "R509") (pin "1") (pinfunction "1_1") (pintype "passive"))
      (node (ref "R510") (pin "1") (pinfunction "1_1") (pintype "passive"))
      (node (ref "R512") (pin "1") (pinfunction "1_1") (pintype "passive"))
      (node (ref "R514") (pin "1") (pinfunction "1_1") (pintype "passive"))
      (node (ref "R516") (pin "1") (pinfunction "1_1") (pintype "passive"))
      (node (ref "R518") (pin "1") (pinfunction "1_1") (pintype "passive"))
      (node (ref "R522") (pin "1") (pinfunction "1_1") (pintype "passive"))
      (node (ref "R526") (pin "1") (pinfunction "1_1") (pintype "passive"))
      (node (ref "R528") (pin "1") (pinfunction "1_1") (pintype "passive"))
      (node (ref "R530") (pin "1") (pinfunction "1_1") (pintype "passive"))
      (node (ref "U501") (pin "41") (pinfunction "EGND_41") (pintype "passive"))
      (node (ref "Y501") (pin "2") (pinfunction "GND_2") (pintype "power_in"))
      (node (ref "Y501") (pin "4") (pinfunction "GND_4") (pintype "power_in"))
    )
    (net (code "49") (name "GND_E") (class "Default")
      (node (ref "C523") (pin "2") (pinfunction "2_2") (pintype "passive"))
      (node (ref "J501") (pin "18") (pinfunction "SHIELD1_18") (pintype "passive"))
      (node (ref "J501") (pin "19") (pinfunction "SHIELD2_19") (pintype "passive"))
      (node (ref "R509") (pin "2") (pinfunction "2_2") (pintype "passive"))
    )
    (net (code "50") (name "Net-(D503-A)") (class "Default")
      (node (ref "D503") (pin "1") (pinfunction "A_1") (pintype "passive"))
      (node (ref "D504") (pin "1") (pinfunction "A_1") (pintype "passive"))
      (node (ref "D505") (pin "1") (pinfunction "A_1") (pintype "passive"))
      (node (ref "Q501") (pin "2") (pinfunction "S_2") (pintype "passive"))
      (node (ref "R524") (pin "1") (pinfunction "1_1") (pintype "passive"))
    )
    (net (code "51") (name "Net-(J501-G_CATODE)") (class "Default")
      (node (ref "J501") (pin "17") (pinfunction "G_CATODE_17") (pintype "passive"))
      (node (ref "R507") (pin "2") (pinfunction "2_2") (pintype "passive"))
    )
    (net (code "52") (name "Net-(J501-O_CATODE)") (class "Default")
      (node (ref "J501") (pin "15") (pinfunction "O_CATODE_15") (pintype "passive"))
      (node (ref "R506") (pin "2") (pinfunction "2_2") (pintype "passive"))
    )
    (net (code "53") (name "Net-(J501-Y_CATODE)") (class "Default")
      (node (ref "J501") (pin "13") (pinfunction "Y_CATODE_13") (pintype "passive"))
      (node (ref "R508") (pin "2") (pinfunction "2_2") (pintype "passive"))
    )
    (net (code "54") (name "PHY1_DVDD3V3") (class "Default")
      (node (ref "C501") (pin "1") (pinfunction "1_1") (pintype "passive"))
      (node (ref "C502") (pin "1") (pinfunction "1_1") (pintype "passive"))
      (node (ref "C520") (pin "1") (pinfunction "1_1") (pintype "passive"))
      (node (ref "FB501") (pin "2") (pinfunction "2_2") (pintype "passive"))
      (node (ref "J501") (pin "14") (pinfunction "Y_ANODE_14") (pintype "passive"))
      (node (ref "J501") (pin "16") (pinfunction "COM_ANODE_16") (pintype "passive"))
      (node (ref "R521") (pin "2") (pinfunction "2_2") (pintype "passive"))
      (node (ref "R525") (pin "2") (pinfunction "2_2") (pintype "passive"))
      (node (ref "R527") (pin "2") (pinfunction "2_2") (pintype "passive"))
      (node (ref "R529") (pin "2") (pinfunction "2_2") (pintype "passive"))
      (node (ref "R531") (pin "2") (pinfunction "2_2") (pintype "passive"))
      (node (ref "U501") (pin "29") (pinfunction "DVDD33_29_29") (pintype "power_in"))
    )
    (net (code "55") (name "PHY1_VDD1V0") (class "Default")
      (node (ref "C514") (pin "2") (pinfunction "2_2") (pintype "passive"))
      (node (ref "C515") (pin "1") (pinfunction "1_1") (pintype "passive"))
      (node (ref "FB502") (pin "2") (pinfunction "2_2") (pintype "passive"))
      (node (ref "FB503") (pin "1") (pinfunction "1_1") (pintype "passive"))
      (node (ref "L501") (pin "2") (pinfunction "2_2") (pintype "passive"))
    )
    (net (code "56") (name "PHY1_VDDIO") (class "Default")
      (node (ref "C505") (pin "1") (pinfunction "1_1") (pintype "passive"))
      (node (ref "C506") (pin "1") (pinfunction "1_1") (pintype "passive"))
      (node (ref "R501") (pin "1") (pinfunction "1_1") (pintype "passive"))
      (node (ref "R511") (pin "2") (pinfunction "2_2") (pintype "passive"))
      (node (ref "R513") (pin "2") (pinfunction "2_2") (pintype "passive"))
      (node (ref "R515") (pin "2") (pinfunction "2_2") (pintype "passive"))
      (node (ref "R517") (pin "2") (pinfunction "2_2") (pintype "passive"))
      (node (ref "R519") (pin "2") (pinfunction "2_2") (pintype "passive"))
      (node (ref "R523") (pin "2") (pinfunction "2_2") (pintype "passive"))
      (node (ref "U501") (pin "28") (pinfunction "DVDD_RG_28") (pintype "power_in"))
    )
  )
)
